# Connectors.net
KiCad netlist of a schematic drawn in Altium Designer
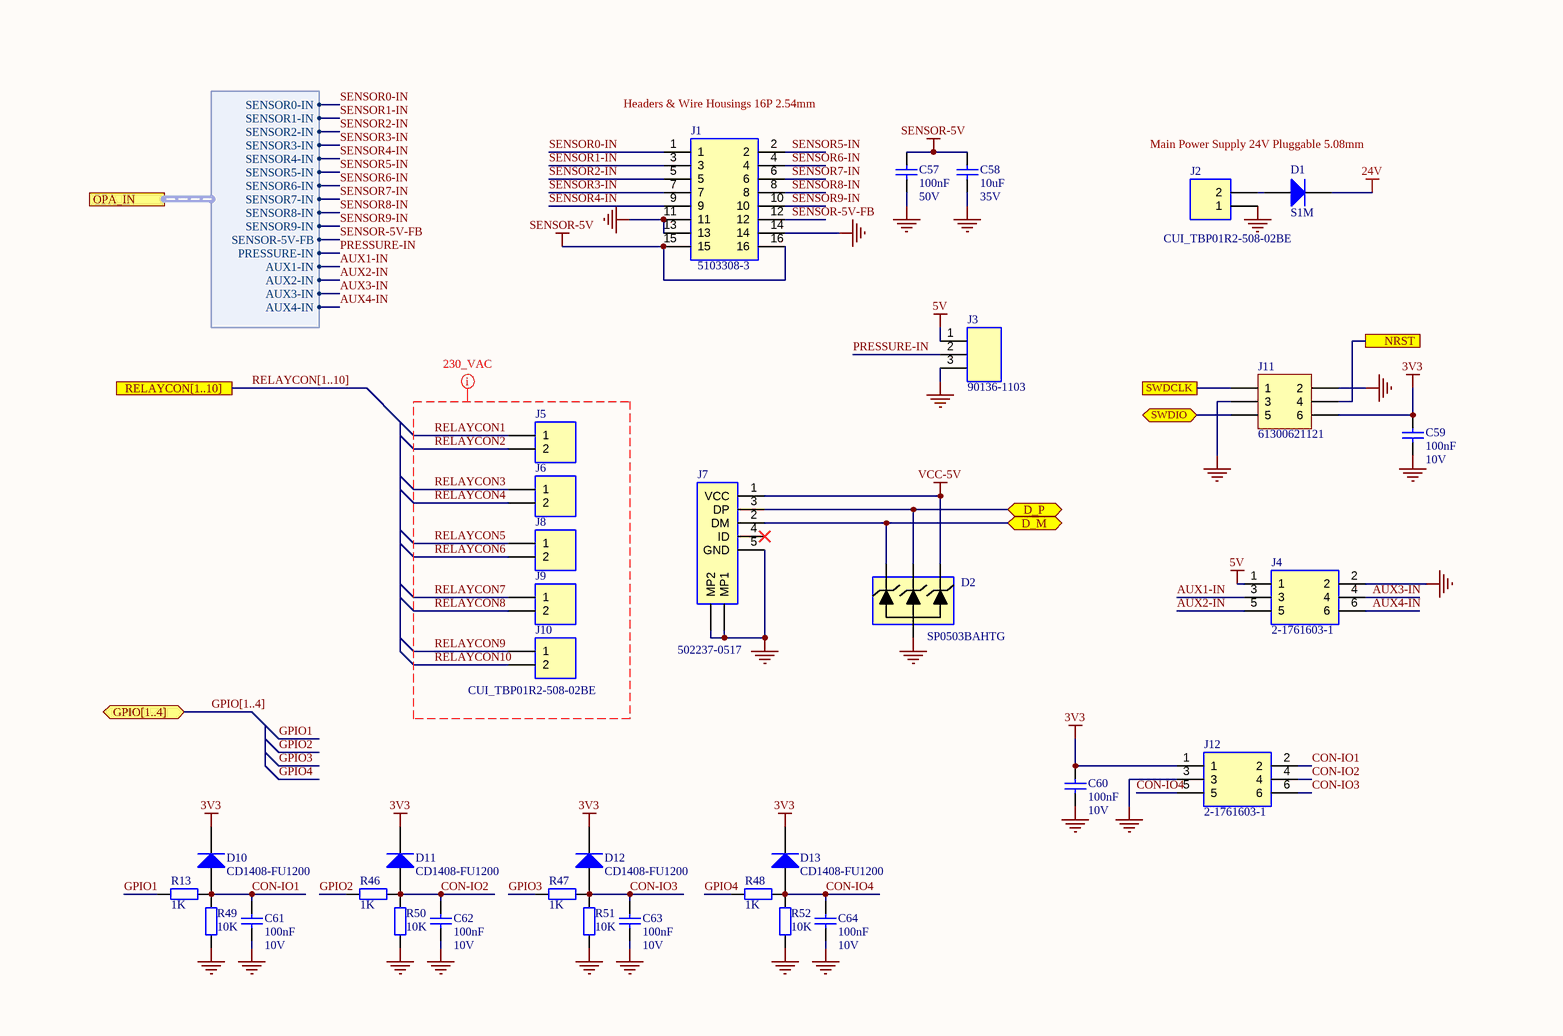
[diagram p0: Connectors.SchDoc]

(export (version "E")
  (design (tool "Eeschema 10.0.6"))
  (components
    (comp (ref "C57")
      (value "Capacitor")
      (footprint "CAPC1608N")
      (fields
        (field (name "PART NUMBER") "CAP-000000002")
        (field (name "VALUE 1") "100nF")
        (field (name "VALUE 2") "50V")
      )
      (libsource (lib "CMA") (part "Capacitor"))
    )
    (comp (ref "C58")
      (value "Capacitor")
      (footprint "CAPC1608N")
      (fields
        (field (name "PART NUMBER") "CAP-000000006")
        (field (name "VALUE 1") "10uF")
        (field (name "VALUE 2") "35V")
      )
      (libsource (lib "CMA") (part "Capacitor"))
    )
    (comp (ref "C59")
      (value "Capacitor")
      (footprint "CAPC1608N")
      (fields
        (field (name "PART NUMBER") "CAP-000000005")
        (field (name "VALUE 1") "100nF")
        (field (name "VALUE 2") "10V")
      )
      (libsource (lib "CMA") (part "Capacitor"))
    )
    (comp (ref "C60")
      (value "Capacitor")
      (footprint "CAPC1608N")
      (fields
        (field (name "PART NUMBER") "CAP-000000005")
        (field (name "VALUE 1") "100nF")
        (field (name "VALUE 2") "10V")
      )
      (libsource (lib "CMA") (part "Capacitor"))
    )
    (comp (ref "C61")
      (value "Capacitor")
      (footprint "CAPC1608N")
      (fields
        (field (name "PART NUMBER") "CAP-000000005")
        (field (name "VALUE 1") "100nF")
        (field (name "VALUE 2") "10V")
      )
      (libsource (lib "CMA") (part "Capacitor"))
    )
    (comp (ref "C62")
      (value "Capacitor")
      (footprint "CAPC1608N")
      (fields
        (field (name "PART NUMBER") "CAP-000000005")
        (field (name "VALUE 1") "100nF")
        (field (name "VALUE 2") "10V")
      )
      (libsource (lib "CMA") (part "Capacitor"))
    )
    (comp (ref "C63")
      (value "Capacitor")
      (footprint "CAPC1608N")
      (fields
        (field (name "PART NUMBER") "CAP-000000005")
        (field (name "VALUE 1") "100nF")
        (field (name "VALUE 2") "10V")
      )
      (libsource (lib "CMA") (part "Capacitor"))
    )
    (comp (ref "C64")
      (value "Capacitor")
      (footprint "CAPC1608N")
      (fields
        (field (name "PART NUMBER") "CAP-000000005")
        (field (name "VALUE 1") "100nF")
        (field (name "VALUE 2") "10V")
      )
      (libsource (lib "CMA") (part "Capacitor"))
    )
    (comp (ref "D1")
      (value "S1M")
      (footprint "DIOM5227X270N")
      (fields (field (name "PART NUMBER") "DIR-000000001"))
      (libsource (lib "CMA") (part "Diode"))
    )
    (comp (ref "D2")
      (value "SP0503BAHTG")
      (footprint "SOT-143")
      (fields (field (name "PART NUMBER") "TVS-000000009"))
      (libsource (lib "CMA") (part "SP0503BAHTG"))
    )
    (comp (ref "D10")
      (value "CD1408-FU1200")
      (footprint "SOD-87")
      (fields (field (name "PART NUMBER") "DIR-000000003"))
      (libsource (lib "CMA") (part "Diode"))
    )
    (comp (ref "D11")
      (value "CD1408-FU1200")
      (footprint "SOD-87")
      (fields (field (name "PART NUMBER") "DIR-000000003"))
      (libsource (lib "CMA") (part "Diode"))
    )
    (comp (ref "D12")
      (value "CD1408-FU1200")
      (footprint "SOD-87")
      (fields (field (name "PART NUMBER") "DIR-000000003"))
      (libsource (lib "CMA") (part "Diode"))
    )
    (comp (ref "D13")
      (value "CD1408-FU1200")
      (footprint "SOD-87")
      (fields (field (name "PART NUMBER") "DIR-000000003"))
      (libsource (lib "CMA") (part "Diode"))
    )
    (comp (ref "J1")
      (value "5103308-3")
      (footprint "5103308-3")
      (fields (field (name "PART NUMBER") "CON-000000002"))
      (libsource (lib "CMA") (part "5103308-3"))
    )
    (comp (ref "J2")
      (value "CUI_TBP01R2-508-02BE")
      (footprint "CUI_TBP01R2-508-02BE")
      (fields (field (name "PART NUMBER") "CON-000000001"))
      (libsource (lib "") (part "Header 2_1"))
    )
    (comp (ref "J3")
      (value "90136-1103")
      (footprint "HDR1X3")
      (fields (field (name "PART NUMBER") "CON-000000004"))
      (libsource (lib "CMA") (part "Header 1X3"))
    )
    (comp (ref "J4")
      (value "2-1761603-1")
      (footprint "2-1761603-1")
      (fields (field (name "PART NUMBER") "CON-000000003"))
      (libsource (lib "CMA") (part "2-1761603-1"))
    )
    (comp (ref "J5")
      (value "CUI_TBP01R2-508-02BE")
      (footprint "CUI_TBP01R2-508-02BE")
      (fields (field (name "PART NUMBER") "CON-000000001"))
      (libsource (lib "CMA") (part "Header 2"))
    )
    (comp (ref "J6")
      (value "CUI_TBP01R2-508-02BE")
      (footprint "CUI_TBP01R2-508-02BE")
      (fields (field (name "PART NUMBER") "CON-000000001"))
      (libsource (lib "CMA") (part "Header 2"))
    )
    (comp (ref "J7")
      (value "502237-0517")
      (footprint "502237-0517")
      (fields (field (name "PART NUMBER") "CON-000000005"))
      (libsource (lib "CMA") (part "USB"))
    )
    (comp (ref "J8")
      (value "CUI_TBP01R2-508-02BE")
      (footprint "CUI_TBP01R2-508-02BE")
      (fields (field (name "PART NUMBER") "CON-000000001"))
      (libsource (lib "CMA") (part "Header 2"))
    )
    (comp (ref "J9")
      (value "CUI_TBP01R2-508-02BE")
      (footprint "CUI_TBP01R2-508-02BE")
      (fields (field (name "PART NUMBER") "CON-000000001"))
      (libsource (lib "CMA") (part "Header 2"))
    )
    (comp (ref "J10")
      (value "CUI_TBP01R2-508-02BE")
      (footprint "CUI_TBP01R2-508-02BE")
      (fields (field (name "PART NUMBER") "CON-000000001"))
      (libsource (lib "CMA") (part "Header 2"))
    )
    (comp (ref "J11")
      (value "61300621121")
      (footprint "HDR2X3")
      (fields (field (name "PART NUMBER") "CON-000000006"))
      (libsource (lib "CMA") (part "Header 2X3"))
    )
    (comp (ref "J12")
      (value "2-1761603-1")
      (footprint "2-1761603-1")
      (fields (field (name "PART NUMBER") "CON-000000003"))
      (libsource (lib "CMA") (part "2-1761603-1"))
    )
    (comp (ref "R13")
      (value "Resistor")
      (footprint "RESC1608N")
      (fields (field (name "PART NUMBER") "RES-000000006") (field (name "VALUE 1") "1K"))
      (libsource (lib "") (part "Resistor_1"))
    )
    (comp (ref "R46")
      (value "Resistor")
      (footprint "RESC1608N")
      (fields (field (name "PART NUMBER") "RES-000000006") (field (name "VALUE 1") "1K"))
      (libsource (lib "") (part "Resistor_1"))
    )
    (comp (ref "R47")
      (value "Resistor")
      (footprint "RESC1608N")
      (fields (field (name "PART NUMBER") "RES-000000006") (field (name "VALUE 1") "1K"))
      (libsource (lib "") (part "Resistor_1"))
    )
    (comp (ref "R48")
      (value "Resistor")
      (footprint "RESC1608N")
      (fields (field (name "PART NUMBER") "RES-000000006") (field (name "VALUE 1") "1K"))
      (libsource (lib "") (part "Resistor_1"))
    )
    (comp (ref "R49")
      (value "Resistor")
      (footprint "RESC1608N")
      (fields (field (name "PART NUMBER") "RES-000000001") (field (name "VALUE 1") "10K"))
      (libsource (lib "CMA") (part "Resistor"))
    )
    (comp (ref "R50")
      (value "Resistor")
      (footprint "RESC1608N")
      (fields (field (name "PART NUMBER") "RES-000000001") (field (name "VALUE 1") "10K"))
      (libsource (lib "CMA") (part "Resistor"))
    )
    (comp (ref "R51")
      (value "Resistor")
      (footprint "RESC1608N")
      (fields (field (name "PART NUMBER") "RES-000000001") (field (name "VALUE 1") "10K"))
      (libsource (lib "CMA") (part "Resistor"))
    )
    (comp (ref "R52")
      (value "Resistor")
      (footprint "RESC1608N")
      (fields (field (name "PART NUMBER") "RES-000000001") (field (name "VALUE 1") "10K"))
      (libsource (lib "CMA") (part "Resistor"))
    )
  )
  (nets
    (net (code "2") (name "/AUX1-IN") (class "Default")
      (node (ref "J4") (pin "3") (pinfunction "3_3") (pintype "passive"))
    )
    (net (code "3") (name "/AUX2-IN") (class "Default")
      (node (ref "J4") (pin "5") (pinfunction "5_5") (pintype "passive"))
    )
    (net (code "4") (name "/AUX3-IN") (class "Default")
      (node (ref "J4") (pin "4") (pinfunction "4_4") (pintype "passive"))
    )
    (net (code "5") (name "/AUX4-IN") (class "Default")
      (node (ref "J4") (pin "6") (pinfunction "6_6") (pintype "passive"))
    )
    (net (code "6") (name "/CON-IO1") (class "Default")
      (node (ref "C61") (pin "2") (pinfunction "2_2") (pintype "passive"))
      (node (ref "D10") (pin "2") (pinfunction "A_2") (pintype "passive"))
      (node (ref "J12") (pin "2") (pinfunction "2_2") (pintype "passive"))
      (node (ref "R13") (pin "1") (pinfunction "1_1") (pintype "passive"))
      (node (ref "R49") (pin "1") (pinfunction "1_1") (pintype "passive"))
    )
    (net (code "7") (name "/CON-IO2") (class "Default")
      (node (ref "C62") (pin "2") (pinfunction "2_2") (pintype "passive"))
      (node (ref "D11") (pin "2") (pinfunction "A_2") (pintype "passive"))
      (node (ref "J12") (pin "4") (pinfunction "4_4") (pintype "passive"))
      (node (ref "R46") (pin "1") (pinfunction "1_1") (pintype "passive"))
      (node (ref "R50") (pin "1") (pinfunction "1_1") (pintype "passive"))
    )
    (net (code "8") (name "/CON-IO3") (class "Default")
      (node (ref "C63") (pin "2") (pinfunction "2_2") (pintype "passive"))
      (node (ref "D12") (pin "2") (pinfunction "A_2") (pintype "passive"))
      (node (ref "J12") (pin "6") (pinfunction "6_6") (pintype "passive"))
      (node (ref "R47") (pin "1") (pinfunction "1_1") (pintype "passive"))
      (node (ref "R51") (pin "1") (pinfunction "1_1") (pintype "passive"))
    )
    (net (code "9") (name "/CON-IO4") (class "Default")
      (node (ref "C64") (pin "2") (pinfunction "2_2") (pintype "passive"))
      (node (ref "D13") (pin "2") (pinfunction "A_2") (pintype "passive"))
      (node (ref "J12") (pin "5") (pinfunction "5_5") (pintype "passive"))
      (node (ref "R48") (pin "1") (pinfunction "1_1") (pintype "passive"))
      (node (ref "R52") (pin "1") (pinfunction "1_1") (pintype "passive"))
    )
    (net (code "10") (name "/D_M") (class "Default")
      (node (ref "D2") (pin "2") (pinfunction "2_2") (pintype "passive"))
      (node (ref "J7") (pin "2") (pinfunction "DM_2") (pintype "passive"))
    )
    (net (code "11") (name "/D_P") (class "Default")
      (node (ref "D2") (pin "3") (pinfunction "3_3") (pintype "passive"))
      (node (ref "J7") (pin "3") (pinfunction "DP_3") (pintype "passive"))
    )
    (net (code "12") (name "/GPIO1") (class "Default")
      (node (ref "R13") (pin "2") (pinfunction "2_2") (pintype "passive"))
    )
    (net (code "13") (name "/GPIO2") (class "Default")
      (node (ref "R46") (pin "2") (pinfunction "2_2") (pintype "passive"))
    )
    (net (code "14") (name "/GPIO3") (class "Default")
      (node (ref "R47") (pin "2") (pinfunction "2_2") (pintype "passive"))
    )
    (net (code "15") (name "/GPIO4") (class "Default")
      (node (ref "R48") (pin "2") (pinfunction "2_2") (pintype "passive"))
    )
    (net (code "17") (name "/NRST") (class "Default")
      (node (ref "J11") (pin "4") (pinfunction "4_4") (pintype "passive"))
    )
    (net (code "18") (name "/PRESSURE-IN") (class "Default")
      (node (ref "J3") (pin "2") (pinfunction "2_2") (pintype "passive"))
    )
    (net (code "19") (name "/RELAYCON1") (class "Default")
      (node (ref "J5") (pin "1") (pinfunction "1_1") (pintype "passive"))
    )
    (net (code "20") (name "/RELAYCON2") (class "Default")
      (node (ref "J5") (pin "2") (pinfunction "2_2") (pintype "passive"))
    )
    (net (code "21") (name "/RELAYCON3") (class "Default")
      (node (ref "J6") (pin "1") (pinfunction "1_1") (pintype "passive"))
    )
    (net (code "22") (name "/RELAYCON4") (class "Default")
      (node (ref "J6") (pin "2") (pinfunction "2_2") (pintype "passive"))
    )
    (net (code "23") (name "/RELAYCON5") (class "Default")
      (node (ref "J8") (pin "1") (pinfunction "1_1") (pintype "passive"))
    )
    (net (code "24") (name "/RELAYCON6") (class "Default")
      (node (ref "J8") (pin "2") (pinfunction "2_2") (pintype "passive"))
    )
    (net (code "25") (name "/RELAYCON7") (class "Default")
      (node (ref "J9") (pin "1") (pinfunction "1_1") (pintype "passive"))
    )
    (net (code "26") (name "/RELAYCON8") (class "Default")
      (node (ref "J9") (pin "2") (pinfunction "2_2") (pintype "passive"))
    )
    (net (code "27") (name "/RELAYCON9") (class "Default")
      (node (ref "J10") (pin "1") (pinfunction "1_1") (pintype "passive"))
    )
    (net (code "28") (name "/RELAYCON10") (class "Default")
      (node (ref "J10") (pin "2") (pinfunction "2_2") (pintype "passive"))
    )
    (net (code "30") (name "/SENSOR-5V-FB") (class "Default")
      (node (ref "J1") (pin "12") (pinfunction "12_12") (pintype "passive"))
    )
    (net (code "31") (name "/SENSOR0-IN") (class "Default")
      (node (ref "J1") (pin "1") (pinfunction "1_1") (pintype "passive"))
    )
    (net (code "32") (name "/SENSOR1-IN") (class "Default")
      (node (ref "J1") (pin "3") (pinfunction "3_3") (pintype "passive"))
    )
    (net (code "33") (name "/SENSOR2-IN") (class "Default")
      (node (ref "J1") (pin "5") (pinfunction "5_5") (pintype "passive"))
    )
    (net (code "34") (name "/SENSOR3-IN") (class "Default")
      (node (ref "J1") (pin "7") (pinfunction "7_7") (pintype "passive"))
    )
    (net (code "35") (name "/SENSOR4-IN") (class "Default")
      (node (ref "J1") (pin "9") (pinfunction "9_9") (pintype "passive"))
    )
    (net (code "36") (name "/SENSOR5-IN") (class "Default")
      (node (ref "J1") (pin "2") (pinfunction "2_2") (pintype "passive"))
    )
    (net (code "37") (name "/SENSOR6-IN") (class "Default")
      (node (ref "J1") (pin "4") (pinfunction "4_4") (pintype "passive"))
    )
    (net (code "38") (name "/SENSOR7-IN") (class "Default")
      (node (ref "J1") (pin "6") (pinfunction "6_6") (pintype "passive"))
    )
    (net (code "39") (name "/SENSOR8-IN") (class "Default")
      (node (ref "J1") (pin "8") (pinfunction "8_8") (pintype "passive"))
    )
    (net (code "40") (name "/SENSOR9-IN") (class "Default")
      (node (ref "J1") (pin "10") (pinfunction "10_10") (pintype "passive"))
    )
    (net (code "41") (name "/SWDCLK") (class "Default")
      (node (ref "J11") (pin "1") (pinfunction "1_1") (pintype "passive"))
    )
    (net (code "42") (name "/SWDIO") (class "Default")
      (node (ref "J11") (pin "5") (pinfunction "5_5") (pintype "passive"))
    )
    (net (code "44") (name "3V3") (class "Default")
      (node (ref "C59") (pin "2") (pinfunction "2_2") (pintype "passive"))
      (node (ref "C60") (pin "2") (pinfunction "2_2") (pintype "passive"))
      (node (ref "D10") (pin "1") (pinfunction "K_1") (pintype "passive"))
      (node (ref "D11") (pin "1") (pinfunction "K_1") (pintype "passive"))
      (node (ref "D12") (pin "1") (pinfunction "K_1") (pintype "passive"))
      (node (ref "D13") (pin "1") (pinfunction "K_1") (pintype "passive"))
      (node (ref "J11") (pin "6") (pinfunction "6_6") (pintype "passive"))
      (node (ref "J12") (pin "1") (pinfunction "1_1") (pintype "passive"))
    )
    (net (code "45") (name "5V") (class "Default")
      (node (ref "J3") (pin "1") (pinfunction "1_1") (pintype "passive"))
      (node (ref "J4") (pin "1") (pinfunction "1_1") (pintype "passive"))
    )
    (net (code "46") (name "24V") (class "Default")
      (node (ref "D1") (pin "1") (pinfunction "K_1") (pintype "passive"))
    )
    (net (code "47") (name "GND") (class "Default")
      (node (ref "C57") (pin "2") (pinfunction "2_2") (pintype "passive"))
      (node (ref "C58") (pin "2") (pinfunction "2_2") (pintype "passive"))
      (node (ref "C59") (pin "1") (pinfunction "1_1") (pintype "passive"))
      (node (ref "C60") (pin "1") (pinfunction "1_1") (pintype "passive"))
      (node (ref "C61") (pin "1") (pinfunction "1_1") (pintype "passive"))
      (node (ref "C62") (pin "1") (pinfunction "1_1") (pintype "passive"))
      (node (ref "C63") (pin "1") (pinfunction "1_1") (pintype "passive"))
      (node (ref "C64") (pin "1") (pinfunction "1_1") (pintype "passive"))
      (node (ref "D2") (pin "1") (pinfunction "1_1") (pintype "passive"))
      (node (ref "J1") (pin "11") (pinfunction "11_11") (pintype "passive"))
      (node (ref "J1") (pin "13") (pinfunction "13_13") (pintype "passive"))
      (node (ref "J1") (pin "14") (pinfunction "14_14") (pintype "passive"))
      (node (ref "J11") (pin "2") (pinfunction "2_2") (pintype "passive"))
      (node (ref "J11") (pin "3") (pinfunction "3_3") (pintype "passive"))
      (node (ref "J12") (pin "3") (pinfunction "3_3") (pintype "passive"))
      (node (ref "J2") (pin "1") (pinfunction "1_1") (pintype "passive"))
      (node (ref "J3") (pin "3") (pinfunction "3_3") (pintype "passive"))
      (node (ref "J4") (pin "2") (pinfunction "2_2") (pintype "passive"))
      (node (ref "J7") (pin "5") (pinfunction "GND_5") (pintype "passive"))
      (node (ref "J7") (pin "MP1") (pinfunction "MP1_MP1") (pintype "passive"))
      (node (ref "J7") (pin "MP2") (pinfunction "MP2_MP2") (pintype "passive"))
      (node (ref "R49") (pin "2") (pinfunction "2_2") (pintype "passive"))
      (node (ref "R50") (pin "2") (pinfunction "2_2") (pintype "passive"))
      (node (ref "R51") (pin "2") (pinfunction "2_2") (pintype "passive"))
      (node (ref "R52") (pin "2") (pinfunction "2_2") (pintype "passive"))
    )
    (net (code "48") (name "Net-(D1-A)") (class "Default")
      (node (ref "D1") (pin "2") (pinfunction "A_2") (pintype "passive"))
      (node (ref "J2") (pin "2") (pinfunction "2_2") (pintype "passive"))
    )
    (net (code "49") (name "SENSOR-5V") (class "Default")
      (node (ref "C57") (pin "1") (pinfunction "1_1") (pintype "passive"))
      (node (ref "C58") (pin "1") (pinfunction "1_1") (pintype "passive"))
      (node (ref "J1") (pin "15") (pinfunction "15_15") (pintype "passive"))
      (node (ref "J1") (pin "16") (pinfunction "16_16") (pintype "passive"))
    )
    (net (code "50") (name "VCC-5V") (class "Default")
      (node (ref "D2") (pin "4") (pinfunction "4_4") (pintype "passive"))
      (node (ref "J7") (pin "1") (pinfunction "VCC_1") (pintype "passive"))
    )
    (net (code "51") (name "unconnected-(J7-ID-Pad4)") (class "Default")
      (node (ref "J7") (pin "4") (pinfunction "ID_4") (pintype "passive+no_connect"))
    )
  )
)
